# 1-Schematic_VineBox.net
KiCad netlist of a schematic drawn in EasyEDA
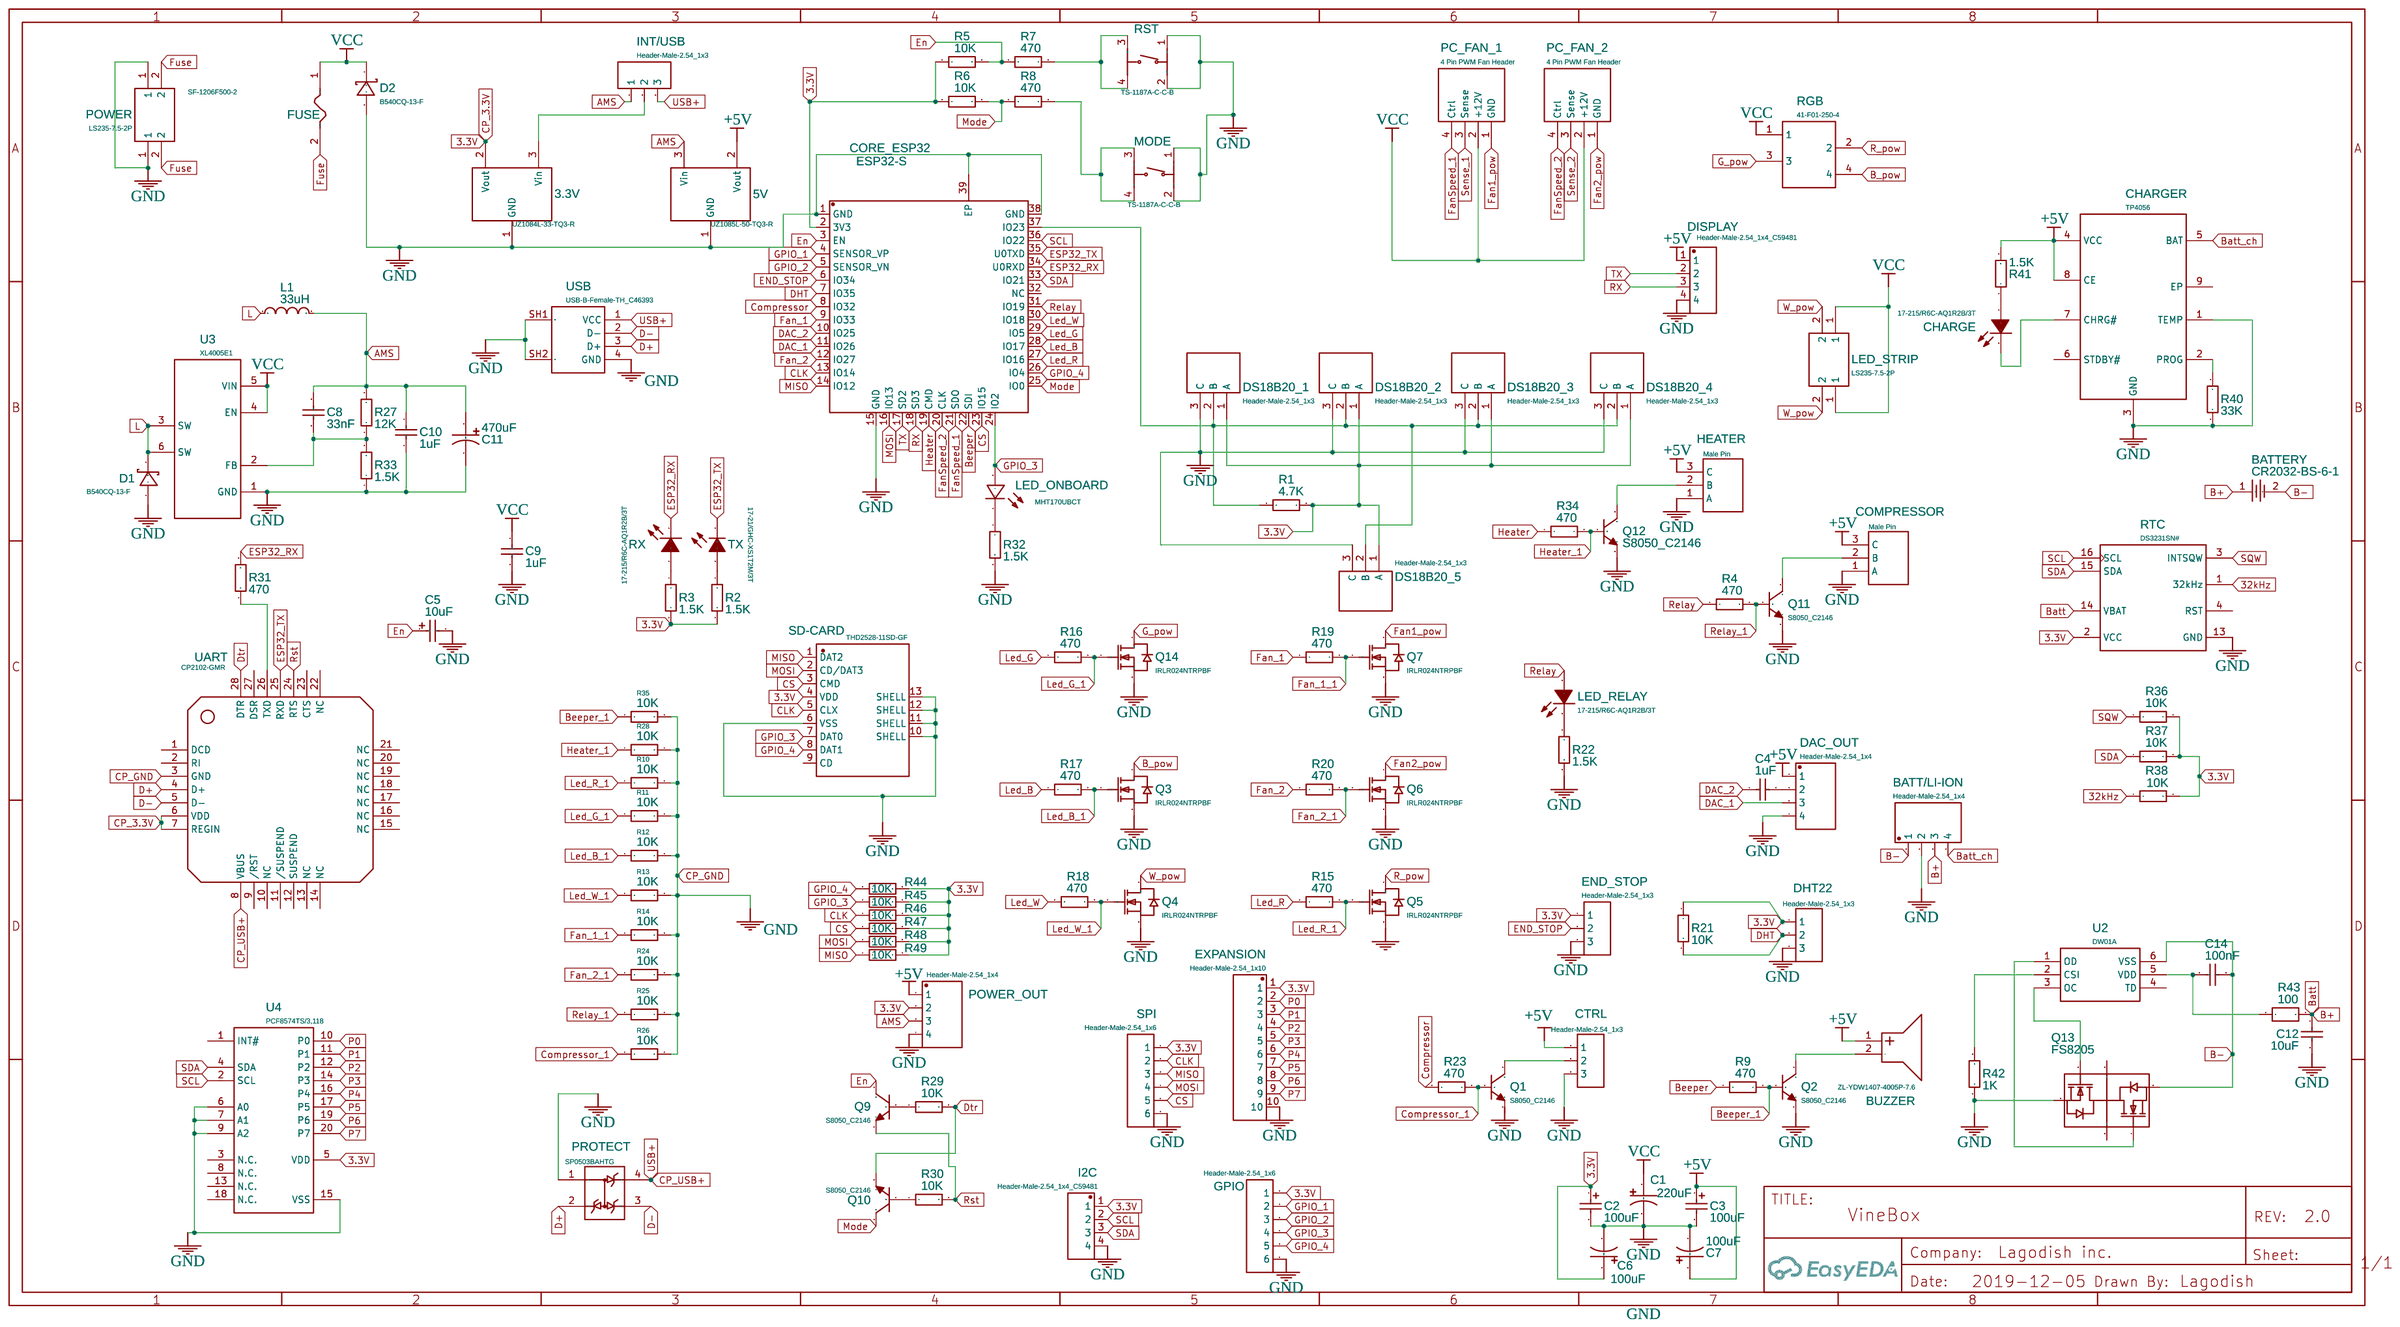
[diagram p0: schematic sheet]

(export (version "E")
  (design (tool "Eeschema 10.0.6"))
  (components
    (comp (ref "3.3V")
      (value "UZ1084L-33-TQ3-R")
      (fields (field (name "BOM_Supplier Part") "C75489"))
      (libsource (lib "") (part "Unknown_280_125"))
    )
    (comp (ref "5V")
      (value "UZ1085L-50-TQ3-R")
      (fields (field (name "BOM_Supplier Part") "C75492"))
      (libsource (lib "") (part "Unknown_430_125"))
    )
    (comp (ref "BATT/LI-ION")
      (value "Header-Male-2.54_1x4")
      (fields
        (field (name "BOM_Manufacturer Part") "210S-1*4P L=11.6MMGold-plated black")
        (field (name "BOM_Supplier Part") "C124378")
      )
      (libsource (lib "") (part "Unknown_1350_605"))
    )
    (comp (ref "BATTERY")
      (value "CR2032-BS-6-1")
      (fields (field (name "BOM_Supplier Part") "C70377"))
      (libsource (lib "") (part "Unknown_1600_350"))
    )
    (comp (ref "BUZZER")
      (value "ZL-YDW1407-4005P-7.6")
      (fields (field (name "BOM_Supplier Part") "C219740"))
      (libsource (lib "") (part "Unknown_1315_765"))
    )
    (comp (ref "C1")
      (value "220uF")
      (fields
        (field (name "BOM_Manufacturer Part") "OVG221M1E1010-TRO")
        (field (name "BOM_Supplier Part") "C250054")
      )
      (libsource (lib "") (part "OVG221M1E1010-TRO"))
    )
    (comp (ref "C2")
      (value "100uF")
      (fields
        (field (name "BOM_Manufacturer Part") "TAJB107K006RNJ")
        (field (name "BOM_Supplier Part") "C16133")
      )
      (libsource (lib "") (part "TAJB107K006RNJ"))
    )
    (comp (ref "C3")
      (value "100uF")
      (fields
        (field (name "BOM_Manufacturer Part") "TAJB107K006RNJ")
        (field (name "BOM_Supplier Part") "C16133")
      )
      (libsource (lib "") (part "TAJB107K006RNJ"))
    )
    (comp (ref "C4")
      (value "1uF")
      (fields
        (field (name "BOM_Manufacturer Part") "CL21B105KBFNNNE")
        (field (name "BOM_Supplier Part") "C28323")
      )
      (libsource (lib "") (part "CL21B105KBFNNNE"))
    )
    (comp (ref "C5")
      (value "10uF")
      (fields
        (field (name "BOM_Manufacturer Part") "TAJA106K016RNJ")
        (field (name "BOM_Supplier Part") "C7171")
      )
      (libsource (lib "") (part "TAJA106K016RNJ"))
    )
    (comp (ref "C6")
      (value "100uF")
      (fields
        (field (name "BOM_Manufacturer Part") "OCV101M0JTR-0606")
        (field (name "BOM_Supplier Part") "C134854")
      )
      (libsource (lib "") (part "OCV101M0JTR-0606_1"))
    )
    (comp (ref "C7")
      (value "100uF")
      (fields
        (field (name "BOM_Manufacturer Part") "OCV101M0JTR-0606")
        (field (name "BOM_Supplier Part") "C134854")
      )
      (libsource (lib "") (part "OCV101M0JTR-0606"))
    )
    (comp (ref "C8")
      (value "33nF")
      (fields
        (field (name "BOM_Manufacturer Part") "0805B333K500NT")
        (field (name "BOM_Supplier Part") "C1739")
      )
      (libsource (lib "") (part "0805B333K500NT"))
    )
    (comp (ref "C9")
      (value "1uF")
      (fields
        (field (name "BOM_Manufacturer Part") "CL21B105KBFNNNE")
        (field (name "BOM_Supplier Part") "C28323")
      )
      (libsource (lib "") (part "CL21B105KBFNNNE_1"))
    )
    (comp (ref "C10")
      (value "1uF")
      (fields
        (field (name "BOM_Manufacturer Part") "CL21B105KBFNNNE")
        (field (name "BOM_Supplier Part") "C28323")
      )
      (libsource (lib "") (part "CL21B105KBFNNNE_1"))
    )
    (comp (ref "C11")
      (value "470uF")
      (fields
        (field (name "BOM_Manufacturer Part") "OVZ471M1A1008-TRO")
        (field (name "BOM_Supplier Part") "C250114")
      )
      (libsource (lib "") (part "OVZ471M1A1008-TRO"))
    )
    (comp (ref "C12")
      (value "10uF")
      (fields
        (field (name "BOM_Manufacturer Part") "CL21A106KAYNNNE")
        (field (name "BOM_Supplier Part") "C15850")
      )
      (libsource (lib "") (part "CL21A106KAYNNNE"))
    )
    (comp (ref "C14")
      (value "100nF")
      (fields
        (field (name "BOM_Manufacturer Part") "CL21B104KCFNNNE")
        (field (name "BOM_Supplier Part") "C28233")
      )
      (libsource (lib "") (part "CL21B104KCFNNNE"))
    )
    (comp (ref "CHARGE")
      (value "17-215/R6C-AQ1R2B/3T")
      (fields (field (name "BOM_Supplier Part") "C86865"))
      (libsource (lib "") (part "Unknown_1405_225"))
    )
    (comp (ref "CHARGER")
      (value "TP4056")
      (fields (field (name "BOM_Supplier Part") "C16581"))
      (libsource (lib "") (part "Unknown_1505_220"))
    )
    (comp (ref "COMPRESSOR")
      (value "Male Pin")
      (fields
        (field (name "BOM_Manufacturer Part") "3 pin header")
        (field (name "BOM_Supplier Part") "C49257")
      )
      (libsource (lib "") (part "Unknown_1325_420"))
    )
    (comp (ref "CORE_ESP32")
      (value "ESP32-S")
      (fields (field (name "BOM_Supplier Part") "C277944"))
      (libsource (lib "") (part "Unknown_595_230"))
    )
    (comp (ref "CTRL")
      (value "Header-Male-2.54_1x3")
      (fields
        (field (name "BOM_Manufacturer Part") "Header2.54mm 1*3P")
        (field (name "BOM_Supplier Part") "C49257")
      )
      (libsource (lib "") (part "Unknown_1090_780"))
    )
    (comp (ref "D1")
      (value "B540CQ-13-F")
      (fields (field (name "BOM_Supplier Part") "C105556"))
      (libsource (lib "") (part "Unknown_5_340"))
    )
    (comp (ref "D2")
      (value "B540CQ-13-F")
      (fields (field (name "BOM_Supplier Part") "C105556"))
      (libsource (lib "") (part "Unknown_170_45"))
    )
    (comp (ref "DAC_OUT")
      (value "Header-Male-2.54_1x4")
      (fields
        (field (name "BOM_Manufacturer Part") "210S-1*4P L=11.6MMGold-plated black")
        (field (name "BOM_Supplier Part") "C124378")
      )
      (libsource (lib "") (part "Unknown_1260_580"))
    )
    (comp (ref "DHT22")
      (value "Header-Male-2.54_1x3")
      (fields
        (field (name "BOM_Manufacturer Part") "Header2.54mm 1*3P")
        (field (name "BOM_Supplier Part") "C49257")
      )
      (libsource (lib "") (part "Unknown_1255_685"))
    )
    (comp (ref "DISPLAY")
      (value "Header-Male-2.54_1x4_C59481")
      (fields
        (field (name "BOM_Manufacturer Part") "Headers  Pins 1*4P")
        (field (name "BOM_Supplier Part") "C124378")
      )
      (libsource (lib "") (part "Unknown_1175_190"))
    )
    (comp (ref "DS18B20_1")
      (value "Header-Male-2.54_1x3")
      (fields
        (field (name "BOM_Manufacturer Part") "3 pin header")
        (field (name "BOM_Supplier Part") "C49257")
      )
      (libsource (lib "") (part "Unknown_830_255"))
    )
    (comp (ref "DS18B20_2")
      (value "Header-Male-2.54_1x3")
      (fields
        (field (name "BOM_Manufacturer Part") "3 pin header")
        (field (name "BOM_Supplier Part") "C49257")
      )
      (libsource (lib "") (part "Unknown_930_255"))
    )
    (comp (ref "DS18B20_3")
      (value "Header-Male-2.54_1x3")
      (fields
        (field (name "BOM_Manufacturer Part") "3 pin header")
        (field (name "BOM_Supplier Part") "C49257")
      )
      (libsource (lib "") (part "Unknown_1030_255"))
    )
    (comp (ref "DS18B20_4")
      (value "Header-Male-2.54_1x3")
      (fields
        (field (name "BOM_Manufacturer Part") "3 pin header")
        (field (name "BOM_Supplier Part") "C49257")
      )
      (libsource (lib "") (part "Unknown_1135_255"))
    )
    (comp (ref "DS18B20_5")
      (value "Header-Male-2.54_1x3")
      (fields
        (field (name "BOM_Manufacturer Part") "3 pin header")
        (field (name "BOM_Supplier Part") "C49257")
      )
      (libsource (lib "") (part "Unknown_945_430"))
    )
    (comp (ref "END_STOP")
      (value "Header-Male-2.54_1x3")
      (fields
        (field (name "BOM_Manufacturer Part") "Header2.54mm 1*3P")
        (field (name "BOM_Supplier Part") "C49257")
      )
      (libsource (lib "") (part "Unknown_1095_680"))
    )
    (comp (ref "EXPANSION")
      (value "Header-Male-2.54_1x10")
      (fields
        (field (name "BOM_Manufacturer Part") "Headers  Pins2.54mm1*10P")
        (field (name "BOM_Supplier Part") "C57369")
      )
      (libsource (lib "") (part "Unknown_845_770"))
    )
    (comp (ref "FUSE")
      (value "SF-1206F500-2")
      (fields (field (name "BOM_Supplier Part") "C48332"))
      (libsource (lib "") (part "Unknown_135_60"))
    )
    (comp (ref "GPIO")
      (value "Header-Male-2.54_1x6")
      (fields (field (name "BOM_Supplier Part") "C37208"))
      (libsource (lib "") (part "Unknown_850_905"))
    )
    (comp (ref "HEATER")
      (value "Male Pin")
      (fields
        (field (name "BOM_Manufacturer Part") "3 pin header")
        (field (name "BOM_Supplier Part") "C49257")
      )
      (libsource (lib "") (part "Unknown_1200_365"))
    )
    (comp (ref "I2C")
      (value "Header-Male-2.54_1x4_C59481")
      (fields
        (field (name "BOM_Manufacturer Part") "Headers  Pins 1*4P")
        (field (name "BOM_Supplier Part") "C124378")
      )
      (libsource (lib "") (part "Unknown_715_905"))
    )
    (comp (ref "INT/USB")
      (value "Header-Male-2.54_1x3")
      (fields
        (field (name "BOM_Manufacturer Part") "Header2.54mm 1*3P")
        (field (name "BOM_Supplier Part") "C49257")
      )
      (libsource (lib "") (part "Unknown_380_40"))
    )
    (comp (ref "L1")
      (value "33uH")
      (fields
        (field (name "BOM_Manufacturer Part") "SWRB1207S-330MT")
        (field (name "BOM_Supplier Part") "C169375")
      )
      (libsource (lib "") (part "SWRB1207S-330MT"))
    )
    (comp (ref "LED_ONBOARD")
      (value "MHT170UBCT")
      (fields (field (name "BOM_Supplier Part") "C389525"))
      (libsource (lib "") (part "Unknown_645_350"))
    )
    (comp (ref "LED_RELAY")
      (value "17-215/R6C-AQ1R2B/3T")
      (fields (field (name "BOM_Supplier Part") "C86865"))
      (libsource (lib "") (part "Unknown_1075_505"))
    )
    (comp (ref "LED_STRIP")
      (value "LS235-7.5-2P")
      (fields (field (name "BOM_Supplier Part") "C165215"))
      (libsource (lib "") (part "Unknown_1270_250"))
    )
    (comp (ref "MODE")
      (value "TS-1187A-C-C-B")
      (fields (field (name "BOM_Supplier Part") "C318889"))
      (libsource (lib "") (part "Unknown_760_110"))
    )
    (comp (ref "PC_FAN_1")
      (value "4 Pin PWM Fan Header")
      (fields (field (name "BOM_Supplier Part") "C49257"))
      (libsource (lib "") (part "Unknown_980_30"))
    )
    (comp (ref "PC_FAN_2")
      (value "4 Pin PWM Fan Header")
      (fields (field (name "BOM_Supplier Part") "C49257"))
      (libsource (lib "") (part "Unknown_1060_30"))
    )
    (comp (ref "POWER")
      (value "LS235-7.5-2P")
      (fields (field (name "BOM_Supplier Part") "C165215"))
      (libsource (lib "") (part "Unknown_15_65"))
    )
    (comp (ref "POWER_OUT")
      (value "Header-Male-2.54_1x4")
      (fields
        (field (name "BOM_Manufacturer Part") "210S-1*4P L=11.6MMGold-plated black")
        (field (name "BOM_Supplier Part") "C124378")
      )
      (libsource (lib "") (part "Unknown_600_745"))
    )
    (comp (ref "PROTECT")
      (value "SP0503BAHTG")
      (fields (field (name "BOM_Supplier Part") "C7074"))
      (libsource (lib "") (part "Unknown_355_880"))
    )
    (comp (ref "Q1")
      (value "S8050_C2146")
      (fields (field (name "BOM_Manufacturer Part") "S8050") (field (name "BOM_Supplier Part") "C2146"))
      (libsource (lib "") (part "Unknown_1020_800"))
    )
    (comp (ref "Q2")
      (value "S8050_C2146")
      (fields (field (name "BOM_Manufacturer Part") "S8050") (field (name "BOM_Supplier Part") "C2146"))
      (libsource (lib "") (part "Unknown_1240_800"))
    )
    (comp (ref "Q3")
      (value "IRLR024NTRPBF")
      (fields (field (name "BOM_Supplier Part") "C3007"))
      (libsource (lib "") (part "Unknown_740_575"))
    )
    (comp (ref "Q4")
      (value "IRLR024NTRPBF")
      (fields (field (name "BOM_Supplier Part") "C3007"))
      (libsource (lib "") (part "Unknown_745_660"))
    )
    (comp (ref "Q5")
      (value "IRLR024NTRPBF")
      (fields (field (name "BOM_Supplier Part") "C3007"))
      (libsource (lib "") (part "Unknown_930_660"))
    )
    (comp (ref "Q6")
      (value "IRLR024NTRPBF")
      (fields (field (name "BOM_Supplier Part") "C3007"))
      (libsource (lib "") (part "Unknown_930_575"))
    )
    (comp (ref "Q7")
      (value "IRLR024NTRPBF")
      (fields (field (name "BOM_Supplier Part") "C3007"))
      (libsource (lib "") (part "Unknown_930_475"))
    )
    (comp (ref "Q9")
      (value "S8050_C2146")
      (fields (field (name "BOM_Manufacturer Part") "S8050") (field (name "BOM_Supplier Part") "C2146"))
      (libsource (lib "") (part "Unknown_565_815"))
    )
    (comp (ref "Q10")
      (value "S8050_C2146")
      (fields (field (name "BOM_Manufacturer Part") "S8050") (field (name "BOM_Supplier Part") "C2146"))
      (libsource (lib "") (part "Unknown_565_885"))
    )
    (comp (ref "Q11")
      (value "S8050_C2146")
      (fields (field (name "BOM_Manufacturer Part") "S8050") (field (name "BOM_Supplier Part") "C2146"))
      (libsource (lib "") (part "Unknown_1230_435"))
    )
    (comp (ref "Q12")
      (value "S8050_C2146")
      (fields (field (name "BOM_Manufacturer Part") "S8050") (field (name "BOM_Supplier Part") "C2146"))
      (libsource (lib "") (part "Unknown_1105_380"))
    )
    (comp (ref "Q13")
      (value "FS8205")
      (fields (field (name "BOM_Supplier Part") "C32254"))
      (libsource (lib "") (part "Unknown_1485_810"))
    )
    (comp (ref "Q14")
      (value "IRLR024NTRPBF")
      (fields (field (name "BOM_Supplier Part") "C3007"))
      (libsource (lib "") (part "Unknown_740_475"))
    )
    (comp (ref "R1")
      (value "4.7K")
      (fields
        (field (name "BOM_Manufacturer Part") "0805W8F4701T5E")
        (field (name "BOM_Supplier Part") "C17673")
      )
      (libsource (lib "") (part "0805W8F4701T5E"))
    )
    (comp (ref "R2")
      (value "1.5K")
      (fields
        (field (name "BOM_Manufacturer Part") "0805W8F1501T5E")
        (field (name "BOM_Supplier Part") "C4310")
      )
      (libsource (lib "") (part "0805W8F1501T5E_1"))
    )
    (comp (ref "R3")
      (value "1.5K")
      (fields
        (field (name "BOM_Manufacturer Part") "0805W8F1501T5E")
        (field (name "BOM_Supplier Part") "C4310")
      )
      (libsource (lib "") (part "0805W8F1501T5E_1"))
    )
    (comp (ref "R4")
      (value "470")
      (fields
        (field (name "BOM_Manufacturer Part") "0805W8F4700T5E")
        (field (name "BOM_Supplier Part") "C17710")
      )
      (libsource (lib "") (part "0805W8F4700T5E"))
    )
    (comp (ref "R5")
      (value "10K")
      (fields
        (field (name "BOM_Manufacturer Part") "0805W8F1002T5E")
        (field (name "BOM_Supplier Part") "C17414")
      )
      (libsource (lib "") (part "0805W8F1002T5E"))
    )
    (comp (ref "R6")
      (value "10K")
      (fields
        (field (name "BOM_Manufacturer Part") "0805W8F1002T5E")
        (field (name "BOM_Supplier Part") "C17414")
      )
      (libsource (lib "") (part "0805W8F1002T5E"))
    )
    (comp (ref "R7")
      (value "470")
      (fields
        (field (name "BOM_Manufacturer Part") "0805W8F4700T5E")
        (field (name "BOM_Supplier Part") "C17710")
      )
      (libsource (lib "") (part "0805W8F4700T5E"))
    )
    (comp (ref "R8")
      (value "470")
      (fields
        (field (name "BOM_Manufacturer Part") "0805W8F4700T5E")
        (field (name "BOM_Supplier Part") "C17710")
      )
      (libsource (lib "") (part "0805W8F4700T5E"))
    )
    (comp (ref "R9")
      (value "470")
      (fields
        (field (name "BOM_Manufacturer Part") "0805W8F4700T5E")
        (field (name "BOM_Supplier Part") "C17710")
      )
      (libsource (lib "") (part "0805W8F4700T5E"))
    )
    (comp (ref "R10")
      (value "10K")
      (fields
        (field (name "BOM_Manufacturer Part") "0805W8F1002T5E")
        (field (name "BOM_Supplier Part") "C17414")
      )
      (libsource (lib "") (part "0805W8F1002T5E"))
    )
    (comp (ref "R11")
      (value "10K")
      (fields
        (field (name "BOM_Manufacturer Part") "0805W8F1002T5E")
        (field (name "BOM_Supplier Part") "C17414")
      )
      (libsource (lib "") (part "0805W8F1002T5E"))
    )
    (comp (ref "R12")
      (value "10K")
      (fields
        (field (name "BOM_Manufacturer Part") "0805W8F1002T5E")
        (field (name "BOM_Supplier Part") "C17414")
      )
      (libsource (lib "") (part "0805W8F1002T5E"))
    )
    (comp (ref "R13")
      (value "10K")
      (fields
        (field (name "BOM_Manufacturer Part") "0805W8F1002T5E")
        (field (name "BOM_Supplier Part") "C17414")
      )
      (libsource (lib "") (part "0805W8F1002T5E"))
    )
    (comp (ref "R14")
      (value "10K")
      (fields
        (field (name "BOM_Manufacturer Part") "0805W8F1002T5E")
        (field (name "BOM_Supplier Part") "C17414")
      )
      (libsource (lib "") (part "0805W8F1002T5E"))
    )
    (comp (ref "R15")
      (value "470")
      (fields
        (field (name "BOM_Manufacturer Part") "0805W8F4700T5E")
        (field (name "BOM_Supplier Part") "C17710")
      )
      (libsource (lib "") (part "0805W8F4700T5E"))
    )
    (comp (ref "R16")
      (value "470")
      (fields
        (field (name "BOM_Manufacturer Part") "0805W8F4700T5E")
        (field (name "BOM_Supplier Part") "C17710")
      )
      (libsource (lib "") (part "0805W8F4700T5E"))
    )
    (comp (ref "R17")
      (value "470")
      (fields
        (field (name "BOM_Manufacturer Part") "0805W8F4700T5E")
        (field (name "BOM_Supplier Part") "C17710")
      )
      (libsource (lib "") (part "0805W8F4700T5E"))
    )
    (comp (ref "R18")
      (value "470")
      (fields
        (field (name "BOM_Manufacturer Part") "0805W8F4700T5E")
        (field (name "BOM_Supplier Part") "C17710")
      )
      (libsource (lib "") (part "0805W8F4700T5E"))
    )
    (comp (ref "R19")
      (value "470")
      (fields
        (field (name "BOM_Manufacturer Part") "0805W8F4700T5E")
        (field (name "BOM_Supplier Part") "C17710")
      )
      (libsource (lib "") (part "0805W8F4700T5E"))
    )
    (comp (ref "R20")
      (value "470")
      (fields
        (field (name "BOM_Manufacturer Part") "0805W8F4700T5E")
        (field (name "BOM_Supplier Part") "C17710")
      )
      (libsource (lib "") (part "0805W8F4700T5E"))
    )
    (comp (ref "R21")
      (value "10K")
      (fields
        (field (name "BOM_Manufacturer Part") "0805W8F1002T5E")
        (field (name "BOM_Supplier Part") "C17414")
      )
      (libsource (lib "") (part "0805W8F1002T5E_1"))
    )
    (comp (ref "R22")
      (value "1.5K")
      (fields
        (field (name "BOM_Manufacturer Part") "0805W8F1501T5E")
        (field (name "BOM_Supplier Part") "C4310")
      )
      (libsource (lib "") (part "0805W8F1501T5E_1"))
    )
    (comp (ref "R23")
      (value "470")
      (fields
        (field (name "BOM_Manufacturer Part") "0805W8F4700T5E")
        (field (name "BOM_Supplier Part") "C17710")
      )
      (libsource (lib "") (part "0805W8F4700T5E"))
    )
    (comp (ref "R24")
      (value "10K")
      (fields
        (field (name "BOM_Manufacturer Part") "0805W8F1002T5E")
        (field (name "BOM_Supplier Part") "C17414")
      )
      (libsource (lib "") (part "0805W8F1002T5E"))
    )
    (comp (ref "R25")
      (value "10K")
      (fields
        (field (name "BOM_Manufacturer Part") "0805W8F1002T5E")
        (field (name "BOM_Supplier Part") "C17414")
      )
      (libsource (lib "") (part "0805W8F1002T5E"))
    )
    (comp (ref "R26")
      (value "10K")
      (fields
        (field (name "BOM_Manufacturer Part") "0805W8F1002T5E")
        (field (name "BOM_Supplier Part") "C17414")
      )
      (libsource (lib "") (part "0805W8F1002T5E"))
    )
    (comp (ref "R27")
      (value "12K")
      (fields
        (field (name "BOM_Manufacturer Part") "RS-05K1202FT")
        (field (name "BOM_Supplier Part") "C136575")
      )
      (libsource (lib "") (part "RS-05K1202FT"))
    )
    (comp (ref "R28")
      (value "10K")
      (fields
        (field (name "BOM_Manufacturer Part") "0805W8F1002T5E")
        (field (name "BOM_Supplier Part") "C17414")
      )
      (libsource (lib "") (part "0805W8F1002T5E"))
    )
    (comp (ref "R29")
      (value "10K")
      (fields
        (field (name "BOM_Manufacturer Part") "0805W8F1002T5E")
        (field (name "BOM_Supplier Part") "C17414")
      )
      (libsource (lib "") (part "0805W8F1002T5E"))
    )
    (comp (ref "R30")
      (value "10K")
      (fields
        (field (name "BOM_Manufacturer Part") "0805W8F1002T5E")
        (field (name "BOM_Supplier Part") "C17414")
      )
      (libsource (lib "") (part "0805W8F1002T5E"))
    )
    (comp (ref "R31")
      (value "470")
      (fields
        (field (name "BOM_Manufacturer Part") "0805W8F4700T5E")
        (field (name "BOM_Supplier Part") "C17710")
      )
      (libsource (lib "") (part "0805W8F4700T5E_1"))
    )
    (comp (ref "R32")
      (value "1.5K")
      (fields
        (field (name "BOM_Manufacturer Part") "0805W8F1501T5E")
        (field (name "BOM_Supplier Part") "C4310")
      )
      (libsource (lib "") (part "0805W8F1501T5E_1"))
    )
    (comp (ref "R33")
      (value "1.5K")
      (fields
        (field (name "BOM_Manufacturer Part") "RS-05K152JT")
        (field (name "BOM_Supplier Part") "C304820")
      )
      (libsource (lib "") (part "RS-05K152JT"))
    )
    (comp (ref "R34")
      (value "470")
      (fields
        (field (name "BOM_Manufacturer Part") "0805W8F4700T5E")
        (field (name "BOM_Supplier Part") "C17710")
      )
      (libsource (lib "") (part "0805W8F4700T5E"))
    )
    (comp (ref "R35")
      (value "10K")
      (fields
        (field (name "BOM_Manufacturer Part") "0805W8F1002T5E")
        (field (name "BOM_Supplier Part") "C17414")
      )
      (libsource (lib "") (part "0805W8F1002T5E"))
    )
    (comp (ref "R36")
      (value "10K")
      (fields
        (field (name "BOM_Manufacturer Part") "0805W8F1002T5E")
        (field (name "BOM_Supplier Part") "C17414")
      )
      (libsource (lib "") (part "0805W8F1002T5E"))
    )
    (comp (ref "R37")
      (value "10K")
      (fields
        (field (name "BOM_Manufacturer Part") "0805W8F1002T5E")
        (field (name "BOM_Supplier Part") "C17414")
      )
      (libsource (lib "") (part "0805W8F1002T5E"))
    )
    (comp (ref "R38")
      (value "10K")
      (fields
        (field (name "BOM_Manufacturer Part") "0805W8F1002T5E")
        (field (name "BOM_Supplier Part") "C17414")
      )
      (libsource (lib "") (part "0805W8F1002T5E"))
    )
    (comp (ref "R40")
      (value "33K")
      (fields
        (field (name "BOM_Manufacturer Part") "0805W8F3302T5E")
        (field (name "BOM_Supplier Part") "C17633")
      )
      (libsource (lib "") (part "0805W8F3302T5E"))
    )
    (comp (ref "R41")
      (value "1.5K")
      (fields
        (field (name "BOM_Manufacturer Part") "0805W8F1501T5E")
        (field (name "BOM_Supplier Part") "C4310")
      )
      (libsource (lib "") (part "0805W8F1501T5E"))
    )
    (comp (ref "R42")
      (value "1K")
      (fields
        (field (name "BOM_Manufacturer Part") "0805W8F1001T5E")
        (field (name "BOM_Supplier Part") "C17513")
      )
      (libsource (lib "") (part "0805W8F1001T5E"))
    )
    (comp (ref "R43")
      (value "100")
      (fields
        (field (name "BOM_Manufacturer Part") "SYLE1206JN100RP")
        (field (name "BOM_Supplier Part") "C385916")
      )
      (libsource (lib "") (part "SYLE1206JN100RP"))
    )
    (comp (ref "R44")
      (value "10K")
      (fields
        (field (name "BOM_Manufacturer Part") "0805W8F1002T5E")
        (field (name "BOM_Supplier Part") "C17414")
      )
      (libsource (lib "") (part "0805W8F1002T5E"))
    )
    (comp (ref "R45")
      (value "10K")
      (fields
        (field (name "BOM_Manufacturer Part") "0805W8F1002T5E")
        (field (name "BOM_Supplier Part") "C17414")
      )
      (libsource (lib "") (part "0805W8F1002T5E"))
    )
    (comp (ref "R46")
      (value "10K")
      (fields
        (field (name "BOM_Manufacturer Part") "0805W8F1002T5E")
        (field (name "BOM_Supplier Part") "C17414")
      )
      (libsource (lib "") (part "0805W8F1002T5E"))
    )
    (comp (ref "R47")
      (value "10K")
      (fields
        (field (name "BOM_Manufacturer Part") "0805W8F1002T5E")
        (field (name "BOM_Supplier Part") "C17414")
      )
      (libsource (lib "") (part "0805W8F1002T5E"))
    )
    (comp (ref "R48")
      (value "10K")
      (fields
        (field (name "BOM_Manufacturer Part") "0805W8F1002T5E")
        (field (name "BOM_Supplier Part") "C17414")
      )
      (libsource (lib "") (part "0805W8F1002T5E"))
    )
    (comp (ref "R49")
      (value "10K")
      (fields
        (field (name "BOM_Manufacturer Part") "0805W8F1002T5E")
        (field (name "BOM_Supplier Part") "C17414")
      )
      (libsource (lib "") (part "0805W8F1002T5E"))
    )
    (comp (ref "RGB")
      (value "41-F01-250-4")
      (fields (field (name "BOM_Supplier Part") "C173392"))
      (libsource (lib "") (part "Unknown_1260_95"))
    )
    (comp (ref "RST")
      (value "TS-1187A-C-C-B")
      (fields (field (name "BOM_Supplier Part") "C318889"))
      (libsource (lib "") (part "Unknown_755_25"))
    )
    (comp (ref "RTC")
      (value "DS3231SN#")
      (fields (field (name "BOM_Manufacturer Part") "DS3231SN") (field (name "BOM_Supplier Part") "C9866"))
      (libsource (lib "") (part "Unknown_1520_430"))
    )
    (comp (ref "RX")
      (value "17-215/R6C-AQ1R2B/3T")
      (fields (field (name "BOM_Supplier Part") "C86865"))
      (libsource (lib "") (part "Unknown_400_390"))
    )
    (comp (ref "SD-CARD")
      (value "THD2528-11SD-GF")
      (fields (field (name "BOM_Supplier Part") "C283232"))
      (libsource (lib "") (part "Unknown_545_515"))
    )
    (comp (ref "SPI")
      (value "Header-Male-2.54_1x6")
      (fields (field (name "BOM_Supplier Part") "C37208"))
      (libsource (lib "") (part "Unknown_760_795"))
    )
    (comp (ref "TX")
      (value "17-21/GHC-XS1T2M/3T")
      (fields (field (name "BOM_Supplier Part") "C63855"))
      (libsource (lib "") (part "Unknown_430_390"))
    )
    (comp (ref "U2")
      (value "DW01A")
      (fields (field (name "BOM_Supplier Part") "C61503"))
      (libsource (lib "") (part "Unknown_1480_715"))
    )
    (comp (ref "U3")
      (value "XL4005E1")
      (fields (field (name "BOM_Supplier Part") "C73332"))
      (libsource (lib "") (part "Unknown_50_310"))
    )
    (comp (ref "U4")
      (value "PCF8574TS/3,118")
      (fields (field (name "BOM_Supplier Part") "C57790"))
      (libsource (lib "") (part "Unknown_100_825"))
    )
    (comp (ref "UART")
      (value "CP2102-GMR")
      (fields (field (name "BOM_Supplier Part") "C6568"))
      (libsource (lib "") (part "Unknown_105_575"))
    )
    (comp (ref "USB")
      (value "USB-B-Female-TH_C46393")
      (fields
        (field (name "BOM_Manufacturer Part") "USB-B-Female-90-TH")
        (field (name "BOM_Supplier Part") "C46393")
      )
      (libsource (lib "") (part "Unknown_330_240"))
    )
  )
  (nets
    (net (code "1") (name "+5V") (class "Default")
      (node (ref "5V") (pin "2") (pinfunction "Vout_2") (pintype "unspecified"))
      (node (ref "BUZZER") (pin "1") (pinfunction "+_1") (pintype "unspecified"))
      (node (ref "C3") (pin "1") (pinfunction "1_1") (pintype "input"))
      (node (ref "C7") (pin "1") (pinfunction "1_1") (pintype "unspecified"))
      (node (ref "CHARGER") (pin "4") (pinfunction "VCC_4") (pintype "unspecified"))
      (node (ref "CHARGER") (pin "8") (pinfunction "CE_8") (pintype "unspecified"))
      (node (ref "COMPRESSOR") (pin "3") (pinfunction "C_3") (pintype "unspecified"))
      (node (ref "CTRL") (pin "1") (pinfunction "1_1") (pintype "input"))
      (node (ref "DAC_OUT") (pin "1") (pinfunction "1_1") (pintype "unspecified"))
      (node (ref "DISPLAY") (pin "1") (pinfunction "1_1") (pintype "unspecified"))
      (node (ref "HEATER") (pin "3") (pinfunction "C_3") (pintype "unspecified"))
      (node (ref "POWER_OUT") (pin "1") (pinfunction "1_1") (pintype "unspecified"))
      (node (ref "R41") (pin "2") (pinfunction "2_2") (pintype "input"))
    )
    (net (code "2") (name "3.3V") (class "Default")
      (node (ref "3.3V") (pin "2") (pinfunction "Vout_2") (pintype "unspecified"))
      (node (ref "C2") (pin "1") (pinfunction "1_1") (pintype "input"))
      (node (ref "C6") (pin "1") (pinfunction "1_1") (pintype "unspecified"))
      (node (ref "CORE_ESP32") (pin "2") (pinfunction "3V3_2") (pintype "unspecified"))
      (node (ref "DHT22") (pin "1") (pinfunction "1_1") (pintype "input"))
      (node (ref "DS18B20_1") (pin "1") (pinfunction "A_1") (pintype "unspecified"))
      (node (ref "DS18B20_2") (pin "1") (pinfunction "A_1") (pintype "unspecified"))
      (node (ref "DS18B20_3") (pin "1") (pinfunction "A_1") (pintype "unspecified"))
      (node (ref "DS18B20_4") (pin "1") (pinfunction "A_1") (pintype "unspecified"))
      (node (ref "DS18B20_5") (pin "1") (pinfunction "A_1") (pintype "unspecified"))
      (node (ref "END_STOP") (pin "1") (pinfunction "1_1") (pintype "input"))
      (node (ref "EXPANSION") (pin "1") (pinfunction "1_1") (pintype "unspecified"))
      (node (ref "GPIO") (pin "1") (pinfunction "1_1") (pintype "input"))
      (node (ref "I2C") (pin "1") (pinfunction "1_1") (pintype "unspecified"))
      (node (ref "POWER_OUT") (pin "2") (pinfunction "2_2") (pintype "unspecified"))
      (node (ref "R1") (pin "2") (pinfunction "2_2") (pintype "input"))
      (node (ref "R2") (pin "2") (pinfunction "2_2") (pintype "input"))
      (node (ref "R21") (pin "1") (pinfunction "1_1") (pintype "input"))
      (node (ref "R3") (pin "2") (pinfunction "2_2") (pintype "input"))
      (node (ref "R36") (pin "2") (pinfunction "2_2") (pintype "input"))
      (node (ref "R37") (pin "2") (pinfunction "2_2") (pintype "input"))
      (node (ref "R38") (pin "2") (pinfunction "2_2") (pintype "input"))
      (node (ref "R44") (pin "2") (pinfunction "2_2") (pintype "input"))
      (node (ref "R45") (pin "2") (pinfunction "2_2") (pintype "input"))
      (node (ref "R46") (pin "2") (pinfunction "2_2") (pintype "input"))
      (node (ref "R47") (pin "2") (pinfunction "2_2") (pintype "input"))
      (node (ref "R48") (pin "2") (pinfunction "2_2") (pintype "input"))
      (node (ref "R49") (pin "2") (pinfunction "2_2") (pintype "input"))
      (node (ref "R5") (pin "1") (pinfunction "1_1") (pintype "input"))
      (node (ref "R6") (pin "1") (pinfunction "1_1") (pintype "input"))
      (node (ref "RTC") (pin "2") (pinfunction "VCC_2") (pintype "passive"))
      (node (ref "SD-CARD") (pin "4") (pinfunction "VDD_4") (pintype "unspecified"))
      (node (ref "SPI") (pin "1") (pinfunction "1_1") (pintype "input"))
      (node (ref "U4") (pin "5") (pinfunction "VDD_5") (pintype "unspecified"))
      (node (ref "UART") (pin "6") (pinfunction "VDD_6") (pintype "unspecified"))
      (node (ref "UART") (pin "7") (pinfunction "REGIN_7") (pintype "unspecified"))
    )
    (net (code "3") (name "32kHz") (class "Default")
      (node (ref "R38") (pin "1") (pinfunction "1_1") (pintype "input"))
      (node (ref "RTC") (pin "1") (pinfunction "32kHz_1") (pintype "unspecified"))
    )
    (net (code "4") (name "AMS") (class "Default")
      (node (ref "5V") (pin "3") (pinfunction "Vin_3") (pintype "unspecified"))
      (node (ref "C10") (pin "1") (pinfunction "1_1") (pintype "input"))
      (node (ref "C11") (pin "1") (pinfunction "1_1") (pintype "unspecified"))
      (node (ref "C8") (pin "2") (pinfunction "2_2") (pintype "input"))
      (node (ref "INT/USB") (pin "1") (pinfunction "1_1") (pintype "input"))
      (node (ref "L1") (pin "2") (pinfunction "2_2") (pintype "unspecified"))
      (node (ref "POWER_OUT") (pin "3") (pinfunction "3_3") (pintype "unspecified"))
      (node (ref "R27") (pin "2") (pinfunction "2_2") (pintype "input"))
    )
    (net (code "5") (name "B+") (class "Default")
      (node (ref "BATT/LI-ION") (pin "3") (pinfunction "3_3") (pintype "unspecified"))
      (node (ref "BATTERY") (pin "1") (pinfunction "1_1") (pintype "input"))
      (node (ref "C12") (pin "1") (pinfunction "1_1") (pintype "input"))
      (node (ref "R43") (pin "2") (pinfunction "2_2") (pintype "unspecified"))
      (node (ref "RTC") (pin "14") (pinfunction "VBAT_14") (pintype "passive"))
    )
    (net (code "6") (name "B-") (class "Default")
      (node (ref "BATT/LI-ION") (pin "1") (pinfunction "1_1") (pintype "unspecified"))
      (node (ref "BATTERY") (pin "2") (pinfunction "2_2") (pintype "input"))
      (node (ref "C14") (pin "2") (pinfunction "2_2") (pintype "input"))
      (node (ref "Q13") (pin "3") (pinfunction "S2_3") (pintype "unspecified"))
      (node (ref "U2") (pin "6") (pinfunction "VSS_6") (pintype "unspecified"))
    )
    (net (code "7") (name "B_pow") (class "Default")
      (node (ref "Q3") (pin "4") (pinfunction "D_4") (pintype "unspecified"))
      (node (ref "RGB") (pin "4") (pinfunction "4_4") (pintype "unspecified"))
    )
    (net (code "8") (name "Batt_ch") (class "Default")
      (node (ref "BATT/LI-ION") (pin "4") (pinfunction "4_4") (pintype "unspecified"))
      (node (ref "CHARGER") (pin "5") (pinfunction "BAT_5") (pintype "unspecified"))
    )
    (net (code "9") (name "Beeper") (class "Default")
      (node (ref "CORE_ESP32") (pin "22") (pinfunction "SDI_22") (pintype "unspecified"))
      (node (ref "R9") (pin "1") (pinfunction "1_1") (pintype "input"))
    )
    (net (code "10") (name "Beeper_1") (class "Default")
      (node (ref "Q2") (pin "1") (pinfunction "B_1") (pintype "unspecified"))
      (node (ref "R35") (pin "1") (pinfunction "1_1") (pintype "input"))
      (node (ref "R9") (pin "2") (pinfunction "2_2") (pintype "input"))
    )
    (net (code "11") (name "CLK") (class "Default")
      (node (ref "CORE_ESP32") (pin "13") (pinfunction "IO14_13") (pintype "unspecified"))
      (node (ref "R46") (pin "1") (pinfunction "1_1") (pintype "input"))
      (node (ref "SD-CARD") (pin "5") (pinfunction "CLX_5") (pintype "unspecified"))
      (node (ref "SPI") (pin "2") (pinfunction "2_2") (pintype "input"))
    )
    (net (code "12") (name "CP_GND") (class "Default")
      (node (ref "3.3V") (pin "1") (pinfunction "GND_1") (pintype "unspecified"))
      (node (ref "5V") (pin "1") (pinfunction "GND_1") (pintype "unspecified"))
      (node (ref "BATT/LI-ION") (pin "2") (pinfunction "2_2") (pintype "unspecified"))
      (node (ref "C1") (pin "2") (pinfunction "2_2") (pintype "unspecified"))
      (node (ref "C10") (pin "2") (pinfunction "2_2") (pintype "input"))
      (node (ref "C11") (pin "2") (pinfunction "2_2") (pintype "unspecified"))
      (node (ref "C12") (pin "2") (pinfunction "2_2") (pintype "input"))
      (node (ref "C2") (pin "2") (pinfunction "2_2") (pintype "input"))
      (node (ref "C3") (pin "2") (pinfunction "2_2") (pintype "input"))
      (node (ref "C5") (pin "2") (pinfunction "2_2") (pintype "input"))
      (node (ref "C6") (pin "2") (pinfunction "2_2") (pintype "unspecified"))
      (node (ref "C7") (pin "2") (pinfunction "2_2") (pintype "unspecified"))
      (node (ref "C9") (pin "2") (pinfunction "2_2") (pintype "input"))
      (node (ref "CHARGER") (pin "1") (pinfunction "TEMP_1") (pintype "unspecified"))
      (node (ref "CHARGER") (pin "3") (pinfunction "GND_3") (pintype "unspecified"))
      (node (ref "COMPRESSOR") (pin "1") (pinfunction "A_1") (pintype "unspecified"))
      (node (ref "CORE_ESP32") (pin "1") (pinfunction "GND_1") (pintype "unspecified"))
      (node (ref "CORE_ESP32") (pin "15") (pinfunction "GND_15") (pintype "unspecified"))
      (node (ref "CORE_ESP32") (pin "38") (pinfunction "GND_38") (pintype "unspecified"))
      (node (ref "CORE_ESP32") (pin "39") (pinfunction "EP_39") (pintype "unspecified"))
      (node (ref "CTRL") (pin "3") (pinfunction "3_3") (pintype "input"))
      (node (ref "D1") (pin "2") (pinfunction "A_2") (pintype "unspecified"))
      (node (ref "D2") (pin "2") (pinfunction "A_2") (pintype "unspecified"))
      (node (ref "DAC_OUT") (pin "4") (pinfunction "4_4") (pintype "unspecified"))
      (node (ref "DHT22") (pin "3") (pinfunction "3_3") (pintype "input"))
      (node (ref "DISPLAY") (pin "4") (pinfunction "4_4") (pintype "unspecified"))
      (node (ref "DS18B20_1") (pin "3") (pinfunction "C_3") (pintype "unspecified"))
      (node (ref "DS18B20_2") (pin "3") (pinfunction "C_3") (pintype "unspecified"))
      (node (ref "DS18B20_3") (pin "3") (pinfunction "C_3") (pintype "unspecified"))
      (node (ref "DS18B20_4") (pin "3") (pinfunction "C_3") (pintype "unspecified"))
      (node (ref "DS18B20_5") (pin "3") (pinfunction "C_3") (pintype "unspecified"))
      (node (ref "END_STOP") (pin "3") (pinfunction "3_3") (pintype "input"))
      (node (ref "EXPANSION") (pin "10") (pinfunction "10_10") (pintype "unspecified"))
      (node (ref "GPIO") (pin "6") (pinfunction "6_6") (pintype "input"))
      (node (ref "HEATER") (pin "1") (pinfunction "A_1") (pintype "unspecified"))
      (node (ref "I2C") (pin "4") (pinfunction "4_4") (pintype "unspecified"))
      (node (ref "MODE") (pin "1") (pinfunction "A_1") (pintype "unspecified"))
      (node (ref "MODE") (pin "2") (pinfunction "B_2") (pintype "unspecified"))
      (node (ref "POWER") (pin "1") (pinfunction "1_1") (pintype "unspecified"))
      (node (ref "POWER_OUT") (pin "4") (pinfunction "4_4") (pintype "unspecified"))
      (node (ref "PROTECT") (pin "1") (pinfunction "1_1") (pintype "input"))
      (node (ref "Q1") (pin "2") (pinfunction "E_2") (pintype "unspecified"))
      (node (ref "Q11") (pin "2") (pinfunction "E_2") (pintype "unspecified"))
      (node (ref "Q12") (pin "2") (pinfunction "E_2") (pintype "unspecified"))
      (node (ref "Q13") (pin "1") (pinfunction "S1_1") (pintype "unspecified"))
      (node (ref "Q14") (pin "3") (pinfunction "S_3") (pintype "unspecified"))
      (node (ref "Q2") (pin "2") (pinfunction "E_2") (pintype "unspecified"))
      (node (ref "Q3") (pin "3") (pinfunction "S_3") (pintype "unspecified"))
      (node (ref "Q4") (pin "3") (pinfunction "S_3") (pintype "unspecified"))
      (node (ref "Q5") (pin "3") (pinfunction "S_3") (pintype "unspecified"))
      (node (ref "Q6") (pin "3") (pinfunction "S_3") (pintype "unspecified"))
      (node (ref "Q7") (pin "3") (pinfunction "S_3") (pintype "unspecified"))
      (node (ref "R10") (pin "2") (pinfunction "2_2") (pintype "input"))
      (node (ref "R11") (pin "2") (pinfunction "2_2") (pintype "input"))
      (node (ref "R12") (pin "2") (pinfunction "2_2") (pintype "input"))
      (node (ref "R13") (pin "2") (pinfunction "2_2") (pintype "input"))
      (node (ref "R14") (pin "2") (pinfunction "2_2") (pintype "input"))
      (node (ref "R22") (pin "2") (pinfunction "2_2") (pintype "input"))
      (node (ref "R24") (pin "2") (pinfunction "2_2") (pintype "input"))
      (node (ref "R25") (pin "2") (pinfunction "2_2") (pintype "input"))
      (node (ref "R26") (pin "2") (pinfunction "2_2") (pintype "input"))
      (node (ref "R28") (pin "2") (pinfunction "2_2") (pintype "input"))
      (node (ref "R32") (pin "2") (pinfunction "2_2") (pintype "input"))
      (node (ref "R33") (pin "1") (pinfunction "1_1") (pintype "unspecified"))
      (node (ref "R35") (pin "2") (pinfunction "2_2") (pintype "input"))
      (node (ref "R40") (pin "2") (pinfunction "2_2") (pintype "input"))
      (node (ref "R42") (pin "1") (pinfunction "1_1") (pintype "input"))
      (node (ref "RST") (pin "1") (pinfunction "A_1") (pintype "unspecified"))
      (node (ref "RST") (pin "2") (pinfunction "B_2") (pintype "unspecified"))
      (node (ref "RTC") (pin "13") (pinfunction "GND_13") (pintype "passive"))
      (node (ref "SD-CARD") (pin "10") (pinfunction "SHELL_10") (pintype "unspecified"))
      (node (ref "SD-CARD") (pin "11") (pinfunction "SHELL_11") (pintype "unspecified"))
      (node (ref "SD-CARD") (pin "12") (pinfunction "SHELL_12") (pintype "unspecified"))
      (node (ref "SD-CARD") (pin "13") (pinfunction "SHELL_13") (pintype "unspecified"))
      (node (ref "SD-CARD") (pin "6") (pinfunction "VSS_6") (pintype "unspecified"))
      (node (ref "SPI") (pin "6") (pinfunction "6_6") (pintype "input"))
      (node (ref "U3") (pin "1") (pinfunction "GND_1") (pintype "unspecified"))
      (node (ref "U4") (pin "15") (pinfunction "VSS_15") (pintype "unspecified"))
      (node (ref "U4") (pin "6") (pinfunction "A0_6") (pintype "unspecified"))
      (node (ref "U4") (pin "7") (pinfunction "A1_7") (pintype "unspecified"))
      (node (ref "U4") (pin "9") (pinfunction "A2_9") (pintype "unspecified"))
      (node (ref "UART") (pin "3") (pinfunction "GND_3") (pintype "unspecified"))
      (node (ref "USB") (pin "4") (pinfunction "GND_4") (pintype "input"))
      (node (ref "USB") (pin "SH1") (pinfunction "SH1_SH1") (pintype "unspecified"))
      (node (ref "USB") (pin "SH2") (pinfunction "SH2_SH2") (pintype "unspecified"))
    )
    (net (code "13") (name "CP_USB+") (class "Default")
      (node (ref "INT/USB") (pin "3") (pinfunction "3_3") (pintype "input"))
      (node (ref "PROTECT") (pin "4") (pinfunction "4_4") (pintype "input"))
      (node (ref "UART") (pin "8") (pinfunction "VBUS_8") (pintype "unspecified"))
      (node (ref "USB") (pin "1") (pinfunction "VCC_1") (pintype "input"))
    )
    (net (code "14") (name "CS") (class "Default")
      (node (ref "CORE_ESP32") (pin "23") (pinfunction "IO15_23") (pintype "unspecified"))
      (node (ref "R47") (pin "1") (pinfunction "1_1") (pintype "input"))
      (node (ref "SD-CARD") (pin "3") (pinfunction "CMD_3") (pintype "unspecified"))
      (node (ref "SPI") (pin "5") (pinfunction "5_5") (pintype "input"))
    )
    (net (code "15") (name "Compressor") (class "Default")
      (node (ref "CORE_ESP32") (pin "8") (pinfunction "IO32_8") (pintype "unspecified"))
      (node (ref "R23") (pin "1") (pinfunction "1_1") (pintype "input"))
    )
    (net (code "16") (name "Compressor_1") (class "Default")
      (node (ref "Q1") (pin "1") (pinfunction "B_1") (pintype "unspecified"))
      (node (ref "R23") (pin "2") (pinfunction "2_2") (pintype "input"))
      (node (ref "R26") (pin "1") (pinfunction "1_1") (pintype "input"))
    )
    (net (code "17") (name "D+") (class "Default")
      (node (ref "PROTECT") (pin "2") (pinfunction "2_2") (pintype "input"))
      (node (ref "UART") (pin "4") (pinfunction "D+_4") (pintype "unspecified"))
      (node (ref "USB") (pin "3") (pinfunction "D+_3") (pintype "input"))
    )
    (net (code "18") (name "D-") (class "Default")
      (node (ref "PROTECT") (pin "3") (pinfunction "3_3") (pintype "input"))
      (node (ref "UART") (pin "5") (pinfunction "D-_5") (pintype "unspecified"))
      (node (ref "USB") (pin "2") (pinfunction "D-_2") (pintype "input"))
    )
    (net (code "19") (name "DAC_1") (class "Default")
      (node (ref "CORE_ESP32") (pin "11") (pinfunction "IO26_11") (pintype "unspecified"))
      (node (ref "DAC_OUT") (pin "3") (pinfunction "3_3") (pintype "unspecified"))
    )
    (net (code "20") (name "DAC_2") (class "Default")
      (node (ref "C4") (pin "1") (pinfunction "1_1") (pintype "input"))
      (node (ref "CORE_ESP32") (pin "10") (pinfunction "IO25_10") (pintype "unspecified"))
    )
    (net (code "21") (name "DHT") (class "Default")
      (node (ref "CORE_ESP32") (pin "7") (pinfunction "IO35_7") (pintype "unspecified"))
      (node (ref "DHT22") (pin "2") (pinfunction "2_2") (pintype "input"))
      (node (ref "R21") (pin "2") (pinfunction "2_2") (pintype "input"))
    )
    (net (code "22") (name "Dtr") (class "Default")
      (node (ref "Q10") (pin "2") (pinfunction "E_2") (pintype "unspecified"))
      (node (ref "R29") (pin "2") (pinfunction "2_2") (pintype "input"))
      (node (ref "UART") (pin "28") (pinfunction "DTR_28") (pintype "unspecified"))
    )
    (net (code "23") (name "END_STOP") (class "Default")
      (node (ref "CORE_ESP32") (pin "6") (pinfunction "IO34_6") (pintype "unspecified"))
      (node (ref "END_STOP") (pin "2") (pinfunction "2_2") (pintype "input"))
    )
    (net (code "24") (name "ESP32_RX") (class "Default")
      (node (ref "CORE_ESP32") (pin "34") (pinfunction "U0RXD_34") (pintype "unspecified"))
      (node (ref "R31") (pin "2") (pinfunction "2_2") (pintype "input"))
      (node (ref "RX") (pin "2") (pinfunction "-_2") (pintype "unspecified"))
    )
    (net (code "25") (name "ESP32_TX") (class "Default")
      (node (ref "CORE_ESP32") (pin "35") (pinfunction "U0TXD_35") (pintype "unspecified"))
      (node (ref "TX") (pin "2") (pinfunction "C_2") (pintype "input"))
      (node (ref "UART") (pin "25") (pinfunction "RXD_25") (pintype "unspecified"))
    )
    (net (code "26") (name "En") (class "Default")
      (node (ref "C5") (pin "1") (pinfunction "1_1") (pintype "input"))
      (node (ref "CORE_ESP32") (pin "3") (pinfunction "EN_3") (pintype "unspecified"))
      (node (ref "Q9") (pin "3") (pinfunction "C_3") (pintype "unspecified"))
      (node (ref "R5") (pin "2") (pinfunction "2_2") (pintype "input"))
      (node (ref "R7") (pin "1") (pinfunction "1_1") (pintype "input"))
    )
    (net (code "27") (name "Fan1_pow") (class "Default")
      (node (ref "PC_FAN_1") (pin "1") (pinfunction "GND_1") (pintype "unspecified"))
      (node (ref "Q7") (pin "4") (pinfunction "D_4") (pintype "unspecified"))
    )
    (net (code "28") (name "Fan2_pow") (class "Default")
      (node (ref "PC_FAN_2") (pin "1") (pinfunction "GND_1") (pintype "unspecified"))
      (node (ref "Q6") (pin "4") (pinfunction "D_4") (pintype "unspecified"))
    )
    (net (code "29") (name "FanSpeed_1") (class "Default")
      (node (ref "CORE_ESP32") (pin "21") (pinfunction "SDO_21") (pintype "unspecified"))
      (node (ref "PC_FAN_1") (pin "4") (pinfunction "Ctrl_4") (pintype "unspecified"))
    )
    (net (code "30") (name "FanSpeed_2") (class "Default")
      (node (ref "CORE_ESP32") (pin "20") (pinfunction "CLK_20") (pintype "unspecified"))
      (node (ref "PC_FAN_2") (pin "4") (pinfunction "Ctrl_4") (pintype "unspecified"))
    )
    (net (code "31") (name "Fan_1") (class "Default")
      (node (ref "CORE_ESP32") (pin "9") (pinfunction "IO33_9") (pintype "unspecified"))
      (node (ref "R19") (pin "1") (pinfunction "1_1") (pintype "input"))
    )
    (net (code "32") (name "Fan_1_1") (class "Default")
      (node (ref "Q7") (pin "1") (pinfunction "G_1") (pintype "unspecified"))
      (node (ref "R14") (pin "1") (pinfunction "1_1") (pintype "input"))
      (node (ref "R19") (pin "2") (pinfunction "2_2") (pintype "input"))
    )
    (net (code "33") (name "Fan_2") (class "Default")
      (node (ref "CORE_ESP32") (pin "12") (pinfunction "IO27_12") (pintype "unspecified"))
      (node (ref "R20") (pin "1") (pinfunction "1_1") (pintype "input"))
    )
    (net (code "34") (name "Fan_2_1") (class "Default")
      (node (ref "Q6") (pin "1") (pinfunction "G_1") (pintype "unspecified"))
      (node (ref "R20") (pin "2") (pinfunction "2_2") (pintype "input"))
      (node (ref "R24") (pin "1") (pinfunction "1_1") (pintype "input"))
    )
    (net (code "35") (name "Fuse") (class "Default")
      (node (ref "FUSE") (pin "2") (pinfunction "2_2") (pintype "unspecified"))
      (node (ref "POWER") (pin "2") (pinfunction "2_2") (pintype "unspecified"))
    )
    (net (code "36") (name "GPIO_1") (class "Default")
      (node (ref "CORE_ESP32") (pin "4") (pinfunction "SENSOR_VP_4") (pintype "unspecified"))
      (node (ref "GPIO") (pin "2") (pinfunction "2_2") (pintype "input"))
    )
    (net (code "37") (name "GPIO_2") (class "Default")
      (node (ref "CORE_ESP32") (pin "5") (pinfunction "SENSOR_VN_5") (pintype "unspecified"))
      (node (ref "GPIO") (pin "3") (pinfunction "3_3") (pintype "input"))
    )
    (net (code "38") (name "GPIO_3") (class "Default")
      (node (ref "CORE_ESP32") (pin "24") (pinfunction "IO2_24") (pintype "unspecified"))
      (node (ref "GPIO") (pin "4") (pinfunction "4_4") (pintype "input"))
      (node (ref "LED_ONBOARD") (pin "2") (pinfunction "+_2") (pintype "unspecified"))
      (node (ref "R45") (pin "1") (pinfunction "1_1") (pintype "input"))
      (node (ref "SD-CARD") (pin "7") (pinfunction "DAT0_7") (pintype "unspecified"))
    )
    (net (code "39") (name "GPIO_4") (class "Default")
      (node (ref "CORE_ESP32") (pin "26") (pinfunction "IO4_26") (pintype "unspecified"))
      (node (ref "GPIO") (pin "5") (pinfunction "5_5") (pintype "input"))
      (node (ref "R44") (pin "1") (pinfunction "1_1") (pintype "input"))
      (node (ref "SD-CARD") (pin "8") (pinfunction "DAT1_8") (pintype "unspecified"))
    )
    (net (code "40") (name "G_pow") (class "Default")
      (node (ref "Q14") (pin "4") (pinfunction "D_4") (pintype "unspecified"))
      (node (ref "RGB") (pin "3") (pinfunction "3_3") (pintype "unspecified"))
    )
    (net (code "41") (name "Heater") (class "Default")
      (node (ref "CORE_ESP32") (pin "19") (pinfunction "CMD_19") (pintype "unspecified"))
      (node (ref "R34") (pin "1") (pinfunction "1_1") (pintype "input"))
    )
    (net (code "42") (name "Heater_1") (class "Default")
      (node (ref "Q12") (pin "1") (pinfunction "B_1") (pintype "unspecified"))
      (node (ref "R28") (pin "1") (pinfunction "1_1") (pintype "input"))
      (node (ref "R34") (pin "2") (pinfunction "2_2") (pintype "input"))
    )
    (net (code "43") (name "L") (class "Default")
      (node (ref "D1") (pin "1") (pinfunction "C_1") (pintype "unspecified"))
      (node (ref "L1") (pin "1") (pinfunction "1_1") (pintype "unspecified"))
      (node (ref "U3") (pin "3") (pinfunction "SW_3") (pintype "unspecified"))
      (node (ref "U3") (pin "6") (pinfunction "SW_6") (pintype "unspecified"))
    )
    (net (code "44") (name "Led_B") (class "Default")
      (node (ref "CORE_ESP32") (pin "28") (pinfunction "IO17_28") (pintype "unspecified"))
      (node (ref "R17") (pin "1") (pinfunction "1_1") (pintype "input"))
    )
    (net (code "45") (name "Led_B_1") (class "Default")
      (node (ref "Q3") (pin "1") (pinfunction "G_1") (pintype "unspecified"))
      (node (ref "R12") (pin "1") (pinfunction "1_1") (pintype "input"))
      (node (ref "R17") (pin "2") (pinfunction "2_2") (pintype "input"))
    )
    (net (code "46") (name "Led_G") (class "Default")
      (node (ref "CORE_ESP32") (pin "29") (pinfunction "IO5_29") (pintype "unspecified"))
      (node (ref "R16") (pin "1") (pinfunction "1_1") (pintype "input"))
    )
    (net (code "47") (name "Led_G_1") (class "Default")
      (node (ref "Q14") (pin "1") (pinfunction "G_1") (pintype "unspecified"))
      (node (ref "R11") (pin "1") (pinfunction "1_1") (pintype "input"))
      (node (ref "R16") (pin "2") (pinfunction "2_2") (pintype "input"))
    )
    (net (code "48") (name "Led_R") (class "Default")
      (node (ref "CORE_ESP32") (pin "27") (pinfunction "IO16_27") (pintype "unspecified"))
      (node (ref "R15") (pin "1") (pinfunction "1_1") (pintype "input"))
    )
    (net (code "49") (name "Led_R_1") (class "Default")
      (node (ref "Q5") (pin "1") (pinfunction "G_1") (pintype "unspecified"))
      (node (ref "R10") (pin "1") (pinfunction "1_1") (pintype "input"))
      (node (ref "R15") (pin "2") (pinfunction "2_2") (pintype "input"))
    )
    (net (code "50") (name "Led_W") (class "Default")
      (node (ref "CORE_ESP32") (pin "30") (pinfunction "IO18_30") (pintype "unspecified"))
      (node (ref "R18") (pin "1") (pinfunction "1_1") (pintype "input"))
    )
    (net (code "51") (name "Led_W_1") (class "Default")
      (node (ref "Q4") (pin "1") (pinfunction "G_1") (pintype "unspecified"))
      (node (ref "R13") (pin "1") (pinfunction "1_1") (pintype "input"))
      (node (ref "R18") (pin "2") (pinfunction "2_2") (pintype "input"))
    )
    (net (code "52") (name "MISO") (class "Default")
      (node (ref "CORE_ESP32") (pin "14") (pinfunction "IO12_14") (pintype "unspecified"))
      (node (ref "R49") (pin "1") (pinfunction "1_1") (pintype "input"))
      (node (ref "SD-CARD") (pin "1") (pinfunction "DAT2_1") (pintype "unspecified"))
      (node (ref "SPI") (pin "3") (pinfunction "3_3") (pintype "input"))
    )
    (net (code "53") (name "MOSI") (class "Default")
      (node (ref "CORE_ESP32") (pin "16") (pinfunction "IO13_16") (pintype "unspecified"))
      (node (ref "R48") (pin "1") (pinfunction "1_1") (pintype "input"))
      (node (ref "SD-CARD") (pin "2") (pinfunction "CD/DAT3_2") (pintype "unspecified"))
      (node (ref "SPI") (pin "4") (pinfunction "4_4") (pintype "input"))
    )
    (net (code "54") (name "Mode") (class "Default")
      (node (ref "CORE_ESP32") (pin "25") (pinfunction "IO0_25") (pintype "unspecified"))
      (node (ref "Q10") (pin "3") (pinfunction "C_3") (pintype "unspecified"))
      (node (ref "R6") (pin "2") (pinfunction "2_2") (pintype "input"))
      (node (ref "R8") (pin "1") (pinfunction "1_1") (pintype "input"))
    )
    (net (code "55") (name "Net-(3.3V-Vin)") (class "Default")
      (node (ref "3.3V") (pin "3") (pinfunction "Vin_3") (pintype "unspecified"))
      (node (ref "INT/USB") (pin "2") (pinfunction "2_2") (pintype "input"))
    )
    (net (code "56") (name "Net-(BUZZER--)") (class "Default")
      (node (ref "BUZZER") (pin "2") (pinfunction "-_2") (pintype "unspecified"))
      (node (ref "Q2") (pin "3") (pinfunction "C_3") (pintype "unspecified"))
    )
    (net (code "57") (name "Net-(C4-Pad2)") (class "Default")
      (node (ref "C4") (pin "2") (pinfunction "2_2") (pintype "input"))
      (node (ref "DAC_OUT") (pin "2") (pinfunction "2_2") (pintype "unspecified"))
    )
    (net (code "58") (name "Net-(CHARGE-+)") (class "Default")
      (node (ref "CHARGE") (pin "1") (pinfunction "+_1") (pintype "unspecified"))
      (node (ref "R41") (pin "1") (pinfunction "1_1") (pintype "input"))
    )
    (net (code "59") (name "Net-(CHARGE--)") (class "Default")
      (node (ref "CHARGE") (pin "2") (pinfunction "-_2") (pintype "unspecified"))
      (node (ref "CHARGER") (pin "7") (pinfunction "CHRG#_7") (pintype "unspecified"))
    )
    (net (code "60") (name "Net-(CHARGER-PROG)") (class "Default")
      (node (ref "CHARGER") (pin "2") (pinfunction "PROG_2") (pintype "unspecified"))
      (node (ref "R40") (pin "1") (pinfunction "1_1") (pintype "input"))
    )
    (net (code "61") (name "Net-(COMPRESSOR-B)") (class "Default")
      (node (ref "COMPRESSOR") (pin "2") (pinfunction "B_2") (pintype "unspecified"))
      (node (ref "Q11") (pin "3") (pinfunction "C_3") (pintype "unspecified"))
    )
    (net (code "62") (name "Net-(CORE_ESP32-IO23)") (class "Default")
      (node (ref "CORE_ESP32") (pin "37") (pinfunction "IO23_37") (pintype "unspecified"))
      (node (ref "DS18B20_1") (pin "2") (pinfunction "B_2") (pintype "unspecified"))
      (node (ref "DS18B20_2") (pin "2") (pinfunction "B_2") (pintype "unspecified"))
      (node (ref "DS18B20_3") (pin "2") (pinfunction "B_2") (pintype "unspecified"))
      (node (ref "DS18B20_4") (pin "2") (pinfunction "B_2") (pintype "unspecified"))
      (node (ref "DS18B20_5") (pin "2") (pinfunction "B_2") (pintype "unspecified"))
      (node (ref "R1") (pin "1") (pinfunction "1_1") (pintype "input"))
    )
    (net (code "63") (name "Net-(HEATER-B)") (class "Default")
      (node (ref "HEATER") (pin "2") (pinfunction "B_2") (pintype "unspecified"))
      (node (ref "Q12") (pin "3") (pinfunction "C_3") (pintype "unspecified"))
    )
    (net (code "64") (name "Net-(LED_ONBOARD--)") (class "Default")
      (node (ref "LED_ONBOARD") (pin "1") (pinfunction "-_1") (pintype "unspecified"))
      (node (ref "R32") (pin "1") (pinfunction "1_1") (pintype "input"))
    )
    (net (code "65") (name "Net-(LED_RELAY--)") (class "Default")
      (node (ref "LED_RELAY") (pin "2") (pinfunction "-_2") (pintype "unspecified"))
      (node (ref "R22") (pin "1") (pinfunction "1_1") (pintype "input"))
    )
    (net (code "66") (name "Net-(MODE-C)") (class "Default")
      (node (ref "MODE") (pin "3") (pinfunction "C_3") (pintype "unspecified"))
      (node (ref "MODE") (pin "4") (pinfunction "D_4") (pintype "unspecified"))
      (node (ref "R8") (pin "2") (pinfunction "2_2") (pintype "input"))
    )
    (net (code "67") (name "Net-(Q1-C)") (class "Default")
      (node (ref "CTRL") (pin "2") (pinfunction "2_2") (pintype "input"))
      (node (ref "Q1") (pin "3") (pinfunction "C_3") (pintype "unspecified"))
    )
    (net (code "68") (name "Net-(Q9-B)") (class "Default")
      (node (ref "Q9") (pin "1") (pinfunction "B_1") (pintype "unspecified"))
      (node (ref "R29") (pin "1") (pinfunction "1_1") (pintype "input"))
    )
    (net (code "69") (name "Net-(Q10-B)") (class "Default")
      (node (ref "Q10") (pin "1") (pinfunction "B_1") (pintype "unspecified"))
      (node (ref "R30") (pin "1") (pinfunction "1_1") (pintype "input"))
    )
    (net (code "70") (name "Net-(Q13-G1)") (class "Default")
      (node (ref "Q13") (pin "6") (pinfunction "G1_6") (pintype "unspecified"))
      (node (ref "U2") (pin "3") (pinfunction "OC_3") (pintype "unspecified"))
    )
    (net (code "71") (name "Net-(Q13-G2)") (class "Default")
      (node (ref "Q13") (pin "4") (pinfunction "G2_4") (pintype "unspecified"))
      (node (ref "U2") (pin "1") (pinfunction "OD_1") (pintype "unspecified"))
    )
    (net (code "72") (name "Net-(RST-C)") (class "Default")
      (node (ref "R7") (pin "2") (pinfunction "2_2") (pintype "input"))
      (node (ref "RST") (pin "3") (pinfunction "C_3") (pintype "unspecified"))
      (node (ref "RST") (pin "4") (pinfunction "D_4") (pintype "unspecified"))
    )
    (net (code "73") (name "Net-(RX-+)") (class "Default")
      (node (ref "R3") (pin "1") (pinfunction "1_1") (pintype "input"))
      (node (ref "RX") (pin "1") (pinfunction "+_1") (pintype "unspecified"))
    )
    (net (code "74") (name "Net-(TX-A)") (class "Default")
      (node (ref "R2") (pin "1") (pinfunction "1_1") (pintype "input"))
      (node (ref "TX") (pin "1") (pinfunction "A_1") (pintype "input"))
    )
    (net (code "75") (name "Net-(U2-CSI)") (class "Default")
      (node (ref "R42") (pin "2") (pinfunction "2_2") (pintype "input"))
      (node (ref "U2") (pin "2") (pinfunction "CSI_2") (pintype "unspecified"))
    )
    (net (code "76") (name "Net-(U2-VDD)") (class "Default")
      (node (ref "C14") (pin "1") (pinfunction "1_1") (pintype "input"))
      (node (ref "R43") (pin "1") (pinfunction "1_1") (pintype "unspecified"))
      (node (ref "U2") (pin "5") (pinfunction "VDD_5") (pintype "unspecified"))
    )
    (net (code "77") (name "Net-(U3-FB)") (class "Default")
      (node (ref "C8") (pin "1") (pinfunction "1_1") (pintype "input"))
      (node (ref "R27") (pin "1") (pinfunction "1_1") (pintype "input"))
      (node (ref "R33") (pin "2") (pinfunction "2_2") (pintype "unspecified"))
      (node (ref "U3") (pin "2") (pinfunction "FB_2") (pintype "unspecified"))
    )
    (net (code "78") (name "Net-(UART-TXD)") (class "Default")
      (node (ref "R31") (pin "1") (pinfunction "1_1") (pintype "input"))
      (node (ref "UART") (pin "26") (pinfunction "TXD_26") (pintype "unspecified"))
    )
    (net (code "79") (name "P0") (class "Default")
      (node (ref "EXPANSION") (pin "2") (pinfunction "2_2") (pintype "unspecified"))
      (node (ref "U4") (pin "10") (pinfunction "P0_10") (pintype "unspecified"))
    )
    (net (code "80") (name "P1") (class "Default")
      (node (ref "EXPANSION") (pin "3") (pinfunction "3_3") (pintype "unspecified"))
      (node (ref "U4") (pin "11") (pinfunction "P1_11") (pintype "unspecified"))
    )
    (net (code "81") (name "P2") (class "Default")
      (node (ref "EXPANSION") (pin "4") (pinfunction "4_4") (pintype "unspecified"))
      (node (ref "U4") (pin "12") (pinfunction "P2_12") (pintype "unspecified"))
    )
    (net (code "82") (name "P3") (class "Default")
      (node (ref "EXPANSION") (pin "5") (pinfunction "5_5") (pintype "unspecified"))
      (node (ref "U4") (pin "14") (pinfunction "P3_14") (pintype "unspecified"))
    )
    (net (code "83") (name "P4") (class "Default")
      (node (ref "EXPANSION") (pin "6") (pinfunction "6_6") (pintype "unspecified"))
      (node (ref "U4") (pin "16") (pinfunction "P4_16") (pintype "unspecified"))
    )
    (net (code "84") (name "P5") (class "Default")
      (node (ref "EXPANSION") (pin "7") (pinfunction "7_7") (pintype "unspecified"))
      (node (ref "U4") (pin "17") (pinfunction "P5_17") (pintype "unspecified"))
    )
    (net (code "85") (name "P6") (class "Default")
      (node (ref "EXPANSION") (pin "8") (pinfunction "8_8") (pintype "unspecified"))
      (node (ref "U4") (pin "19") (pinfunction "P6_19") (pintype "unspecified"))
    )
    (net (code "86") (name "P7") (class "Default")
      (node (ref "EXPANSION") (pin "9") (pinfunction "9_9") (pintype "unspecified"))
      (node (ref "U4") (pin "20") (pinfunction "P7_20") (pintype "unspecified"))
    )
    (net (code "87") (name "RX") (class "Default")
      (node (ref "CORE_ESP32") (pin "18") (pinfunction "SD3_18") (pintype "unspecified"))
      (node (ref "DISPLAY") (pin "3") (pinfunction "3_3") (pintype "unspecified"))
    )
    (net (code "88") (name "R_pow") (class "Default")
      (node (ref "Q5") (pin "4") (pinfunction "D_4") (pintype "unspecified"))
      (node (ref "RGB") (pin "2") (pinfunction "2_2") (pintype "unspecified"))
    )
    (net (code "89") (name "Relay") (class "Default")
      (node (ref "CORE_ESP32") (pin "31") (pinfunction "IO19_31") (pintype "unspecified"))
      (node (ref "LED_RELAY") (pin "1") (pinfunction "+_1") (pintype "unspecified"))
      (node (ref "R4") (pin "1") (pinfunction "1_1") (pintype "input"))
    )
    (net (code "90") (name "Relay_1") (class "Default")
      (node (ref "Q11") (pin "1") (pinfunction "B_1") (pintype "unspecified"))
      (node (ref "R25") (pin "1") (pinfunction "1_1") (pintype "input"))
      (node (ref "R4") (pin "2") (pinfunction "2_2") (pintype "input"))
    )
    (net (code "91") (name "Rst") (class "Default")
      (node (ref "Q9") (pin "2") (pinfunction "E_2") (pintype "unspecified"))
      (node (ref "R30") (pin "2") (pinfunction "2_2") (pintype "input"))
      (node (ref "UART") (pin "24") (pinfunction "RTS_24") (pintype "unspecified"))
    )
    (net (code "92") (name "SCL") (class "Default")
      (node (ref "CORE_ESP32") (pin "36") (pinfunction "IO22_36") (pintype "unspecified"))
      (node (ref "I2C") (pin "2") (pinfunction "2_2") (pintype "unspecified"))
      (node (ref "RTC") (pin "16") (pinfunction "SCL_16") (pintype "unspecified"))
      (node (ref "U4") (pin "2") (pinfunction "SCL_2") (pintype "unspecified"))
    )
    (net (code "93") (name "SDA") (class "Default")
      (node (ref "CORE_ESP32") (pin "33") (pinfunction "IO21_33") (pintype "unspecified"))
      (node (ref "I2C") (pin "3") (pinfunction "3_3") (pintype "unspecified"))
      (node (ref "R37") (pin "1") (pinfunction "1_1") (pintype "input"))
      (node (ref "RTC") (pin "15") (pinfunction "SDA_15") (pintype "bidirectional"))
      (node (ref "U4") (pin "4") (pinfunction "SDA_4") (pintype "unspecified"))
    )
    (net (code "94") (name "SQW") (class "Default")
      (node (ref "R36") (pin "1") (pinfunction "1_1") (pintype "input"))
      (node (ref "RTC") (pin "3") (pinfunction "INTSQW_3") (pintype "unspecified"))
    )
    (net (code "95") (name "Sense_1") (class "Default")
      (node (ref "PC_FAN_1") (pin "3") (pinfunction "Sense_3") (pintype "unspecified"))
    )
    (net (code "96") (name "Sense_2") (class "Default")
      (node (ref "PC_FAN_2") (pin "3") (pinfunction "Sense_3") (pintype "unspecified"))
    )
    (net (code "97") (name "TX") (class "Default")
      (node (ref "CORE_ESP32") (pin "17") (pinfunction "SD2_17") (pintype "unspecified"))
      (node (ref "DISPLAY") (pin "2") (pinfunction "2_2") (pintype "unspecified"))
    )
    (net (code "98") (name "VCC") (class "Default")
      (node (ref "C1") (pin "1") (pinfunction "1_1") (pintype "unspecified"))
      (node (ref "C9") (pin "1") (pinfunction "1_1") (pintype "input"))
      (node (ref "D2") (pin "1") (pinfunction "C_1") (pintype "unspecified"))
      (node (ref "FUSE") (pin "1") (pinfunction "1_1") (pintype "unspecified"))
      (node (ref "LED_STRIP") (pin "1") (pinfunction "1_1") (pintype "unspecified"))
      (node (ref "PC_FAN_1") (pin "2") (pinfunction "+12V_2") (pintype "unspecified"))
      (node (ref "PC_FAN_2") (pin "2") (pinfunction "+12V_2") (pintype "unspecified"))
      (node (ref "RGB") (pin "1") (pinfunction "1_1") (pintype "unspecified"))
      (node (ref "U3") (pin "4") (pinfunction "EN_4") (pintype "unspecified"))
      (node (ref "U3") (pin "5") (pinfunction "VIN_5") (pintype "unspecified"))
    )
    (net (code "99") (name "W_pow") (class "Default")
      (node (ref "LED_STRIP") (pin "2") (pinfunction "2_2") (pintype "unspecified"))
      (node (ref "Q4") (pin "4") (pinfunction "D_4") (pintype "unspecified"))
    )
    (net (code "100") (name "unconnected-(CHARGER-EP-Pad9)") (class "Default")
      (node (ref "CHARGER") (pin "9") (pinfunction "EP_9") (pintype "unspecified"))
    )
    (net (code "101") (name "unconnected-(CHARGER-STDBY#-Pad6)") (class "Default")
      (node (ref "CHARGER") (pin "6") (pinfunction "STDBY#_6") (pintype "unspecified"))
    )
    (net (code "102") (name "unconnected-(CORE_ESP32-NC-Pad32)") (class "Default")
      (node (ref "CORE_ESP32") (pin "32") (pinfunction "NC_32") (pintype "unspecified"))
    )
    (net (code "103") (name "unconnected-(Q13-D12-Pad2)") (class "Default")
      (node (ref "Q13") (pin "2") (pinfunction "D12_2") (pintype "unspecified"))
    )
    (net (code "104") (name "unconnected-(Q13-D12-Pad5)") (class "Default")
      (node (ref "Q13") (pin "5") (pinfunction "D12_5") (pintype "unspecified"))
    )
    (net (code "105") (name "unconnected-(RTC-RST-Pad4)") (class "Default")
      (node (ref "RTC") (pin "4") (pinfunction "RST_4") (pintype "bidirectional"))
    )
    (net (code "106") (name "unconnected-(SD-CARD-CD-Pad9)") (class "Default")
      (node (ref "SD-CARD") (pin "9") (pinfunction "CD_9") (pintype "unspecified"))
    )
    (net (code "107") (name "unconnected-(U2-TD-Pad4)") (class "Default")
      (node (ref "U2") (pin "4") (pinfunction "TD_4") (pintype "unspecified"))
    )
    (net (code "108") (name "unconnected-(U4-INT#-Pad1)") (class "Default")
      (node (ref "U4") (pin "1") (pinfunction "INT#_1") (pintype "unspecified"))
    )
    (net (code "109") (name "unconnected-(U4-N.C.-Pad3)") (class "Default")
      (node (ref "U4") (pin "3") (pinfunction "N.C._3") (pintype "unspecified"))
    )
    (net (code "110") (name "unconnected-(U4-N.C.-Pad8)") (class "Default")
      (node (ref "U4") (pin "8") (pinfunction "N.C._8") (pintype "unspecified"))
    )
    (net (code "111") (name "unconnected-(U4-N.C.-Pad13)") (class "Default")
      (node (ref "U4") (pin "13") (pinfunction "N.C._13") (pintype "unspecified"))
    )
    (net (code "112") (name "unconnected-(U4-N.C.-Pad18)") (class "Default")
      (node (ref "U4") (pin "18") (pinfunction "N.C._18") (pintype "unspecified"))
    )
    (net (code "113") (name "unconnected-(UART-CTS-Pad23)") (class "Default")
      (node (ref "UART") (pin "23") (pinfunction "CTS_23") (pintype "unspecified"))
    )
    (net (code "114") (name "unconnected-(UART-DCD-Pad1)") (class "Default")
      (node (ref "UART") (pin "1") (pinfunction "DCD_1") (pintype "unspecified"))
    )
    (net (code "115") (name "unconnected-(UART-DSR-Pad27)") (class "Default")
      (node (ref "UART") (pin "27") (pinfunction "DSR_27") (pintype "unspecified"))
    )
    (net (code "116") (name "unconnected-(UART-NC-Pad10)") (class "Default")
      (node (ref "UART") (pin "10") (pinfunction "NC_10") (pintype "unspecified"))
    )
    (net (code "117") (name "unconnected-(UART-NC-Pad13)") (class "Default")
      (node (ref "UART") (pin "13") (pinfunction "NC_13") (pintype "unspecified"))
    )
    (net (code "118") (name "unconnected-(UART-NC-Pad14)") (class "Default")
      (node (ref "UART") (pin "14") (pinfunction "NC_14") (pintype "unspecified"))
    )
    (net (code "119") (name "unconnected-(UART-NC-Pad15)") (class "Default")
      (node (ref "UART") (pin "15") (pinfunction "NC_15") (pintype "unspecified"))
    )
    (net (code "120") (name "unconnected-(UART-NC-Pad16)") (class "Default")
      (node (ref "UART") (pin "16") (pinfunction "NC_16") (pintype "unspecified"))
    )
    (net (code "121") (name "unconnected-(UART-NC-Pad17)") (class "Default")
      (node (ref "UART") (pin "17") (pinfunction "NC_17") (pintype "unspecified"))
    )
    (net (code "122") (name "unconnected-(UART-NC-Pad18)") (class "Default")
      (node (ref "UART") (pin "18") (pinfunction "NC_18") (pintype "unspecified"))
    )
    (net (code "123") (name "unconnected-(UART-NC-Pad19)") (class "Default")
      (node (ref "UART") (pin "19") (pinfunction "NC_19") (pintype "unspecified"))
    )
    (net (code "124") (name "unconnected-(UART-NC-Pad20)") (class "Default")
      (node (ref "UART") (pin "20") (pinfunction "NC_20") (pintype "unspecified"))
    )
    (net (code "125") (name "unconnected-(UART-NC-Pad21)") (class "Default")
      (node (ref "UART") (pin "21") (pinfunction "NC_21") (pintype "unspecified"))
    )
    (net (code "126") (name "unconnected-(UART-NC-Pad22)") (class "Default")
      (node (ref "UART") (pin "22") (pinfunction "NC_22") (pintype "unspecified"))
    )
    (net (code "127") (name "unconnected-(UART-RI-Pad2)") (class "Default")
      (node (ref "UART") (pin "2") (pinfunction "RI_2") (pintype "unspecified"))
    )
    (net (code "128") (name "unconnected-(UART-SUSPEND-Pad12)") (class "Default")
      (node (ref "UART") (pin "12") (pinfunction "SUSPEND_12") (pintype "unspecified"))
    )
    (net (code "129") (name "unconnected-(UART-{slash}RST-Pad9)") (class "Default")
      (node (ref "UART") (pin "9") (pinfunction "/RST_9") (pintype "unspecified"))
    )
    (net (code "130") (name "unconnected-(UART-{slash}SUSPEND-Pad11)") (class "Default")
      (node (ref "UART") (pin "11") (pinfunction "/SUSPEND_11") (pintype "unspecified"))
    )
  )
)
